# Motors_State_Monitor.net
KiCad netlist of a schematic drawn in Altium Designer
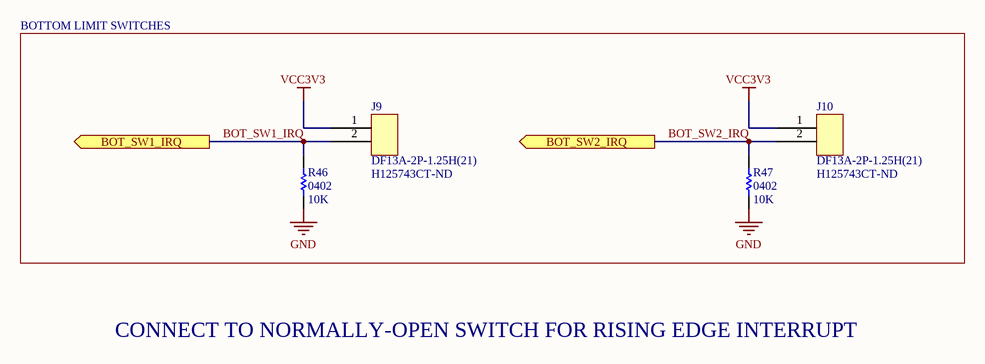
[diagram p0: Motors State Monitor.SchDoc]

(export (version "E")
  (design (tool "Eeschema 10.0.6"))
  (components
    (comp (ref "J9")
      (value "DF13A-2P-1.25H(21)")
      (footprint "DF13A-2P-1.25H(21)")
      (description "2 pos DF13 right angle surface mount connector")
      (fields (field (name "SUPPLIER PART NUMBER 1") "H125743CT-ND"))
      (libsource (lib "DF13A-2P-1.25H(21)") (part "DF13A-2P-1.25H(21)"))
    )
    (comp (ref "J10")
      (value "DF13A-2P-1.25H(21)")
      (footprint "DF13A-2P-1.25H(21)")
      (description "2 pos DF13 right angle surface mount connector")
      (fields (field (name "SUPPLIER PART NUMBER 1") "H125743CT-ND"))
      (libsource (lib "DF13A-2P-1.25H(21)") (part "DF13A-2P-1.25H(21)"))
    )
    (comp (ref "R46")
      (value "0402")
      (footprint "RES0402R")
      (description "0402 resistor")
      (fields
        (field (name "ALTIUM_VALUE") "10K")
        (field (name "MANUFACTURER") "Panasonic")
        (field (name "MANUFACTURER PART NUMBER") "ERJ-2RKF1002X")
      )
      (libsource (lib "heron-general") (part "RES0402"))
    )
    (comp (ref "R47")
      (value "0402")
      (footprint "RES0402R")
      (description "0402 resistor")
      (fields
        (field (name "ALTIUM_VALUE") "10K")
        (field (name "MANUFACTURER") "Panasonic")
        (field (name "MANUFACTURER PART NUMBER") "ERJ-2RKF1002X")
      )
      (libsource (lib "heron-general") (part "RES0402"))
    )
  )
  (nets
    (net (code "1") (name "/BOT_SW1_IRQ") (class "Default")
      (node (ref "J9") (pin "2") (pintype "passive"))
      (node (ref "R46") (pin "2") (pinfunction "2_2") (pintype "passive"))
    )
    (net (code "2") (name "/BOT_SW2_IRQ") (class "Default")
      (node (ref "J10") (pin "2") (pintype "passive"))
      (node (ref "R47") (pin "2") (pinfunction "2_2") (pintype "passive"))
    )
    (net (code "3") (name "GND") (class "Default")
      (node (ref "R46") (pin "1") (pinfunction "1_1") (pintype "passive"))
      (node (ref "R47") (pin "1") (pinfunction "1_1") (pintype "passive"))
    )
    (net (code "4") (name "VCC3V3") (class "Default")
      (node (ref "J10") (pin "1") (pintype "passive"))
      (node (ref "J9") (pin "1") (pintype "passive"))
    )
  )
)
